# ControlBoard.net
KiCad netlist of a schematic drawn in EAGLE
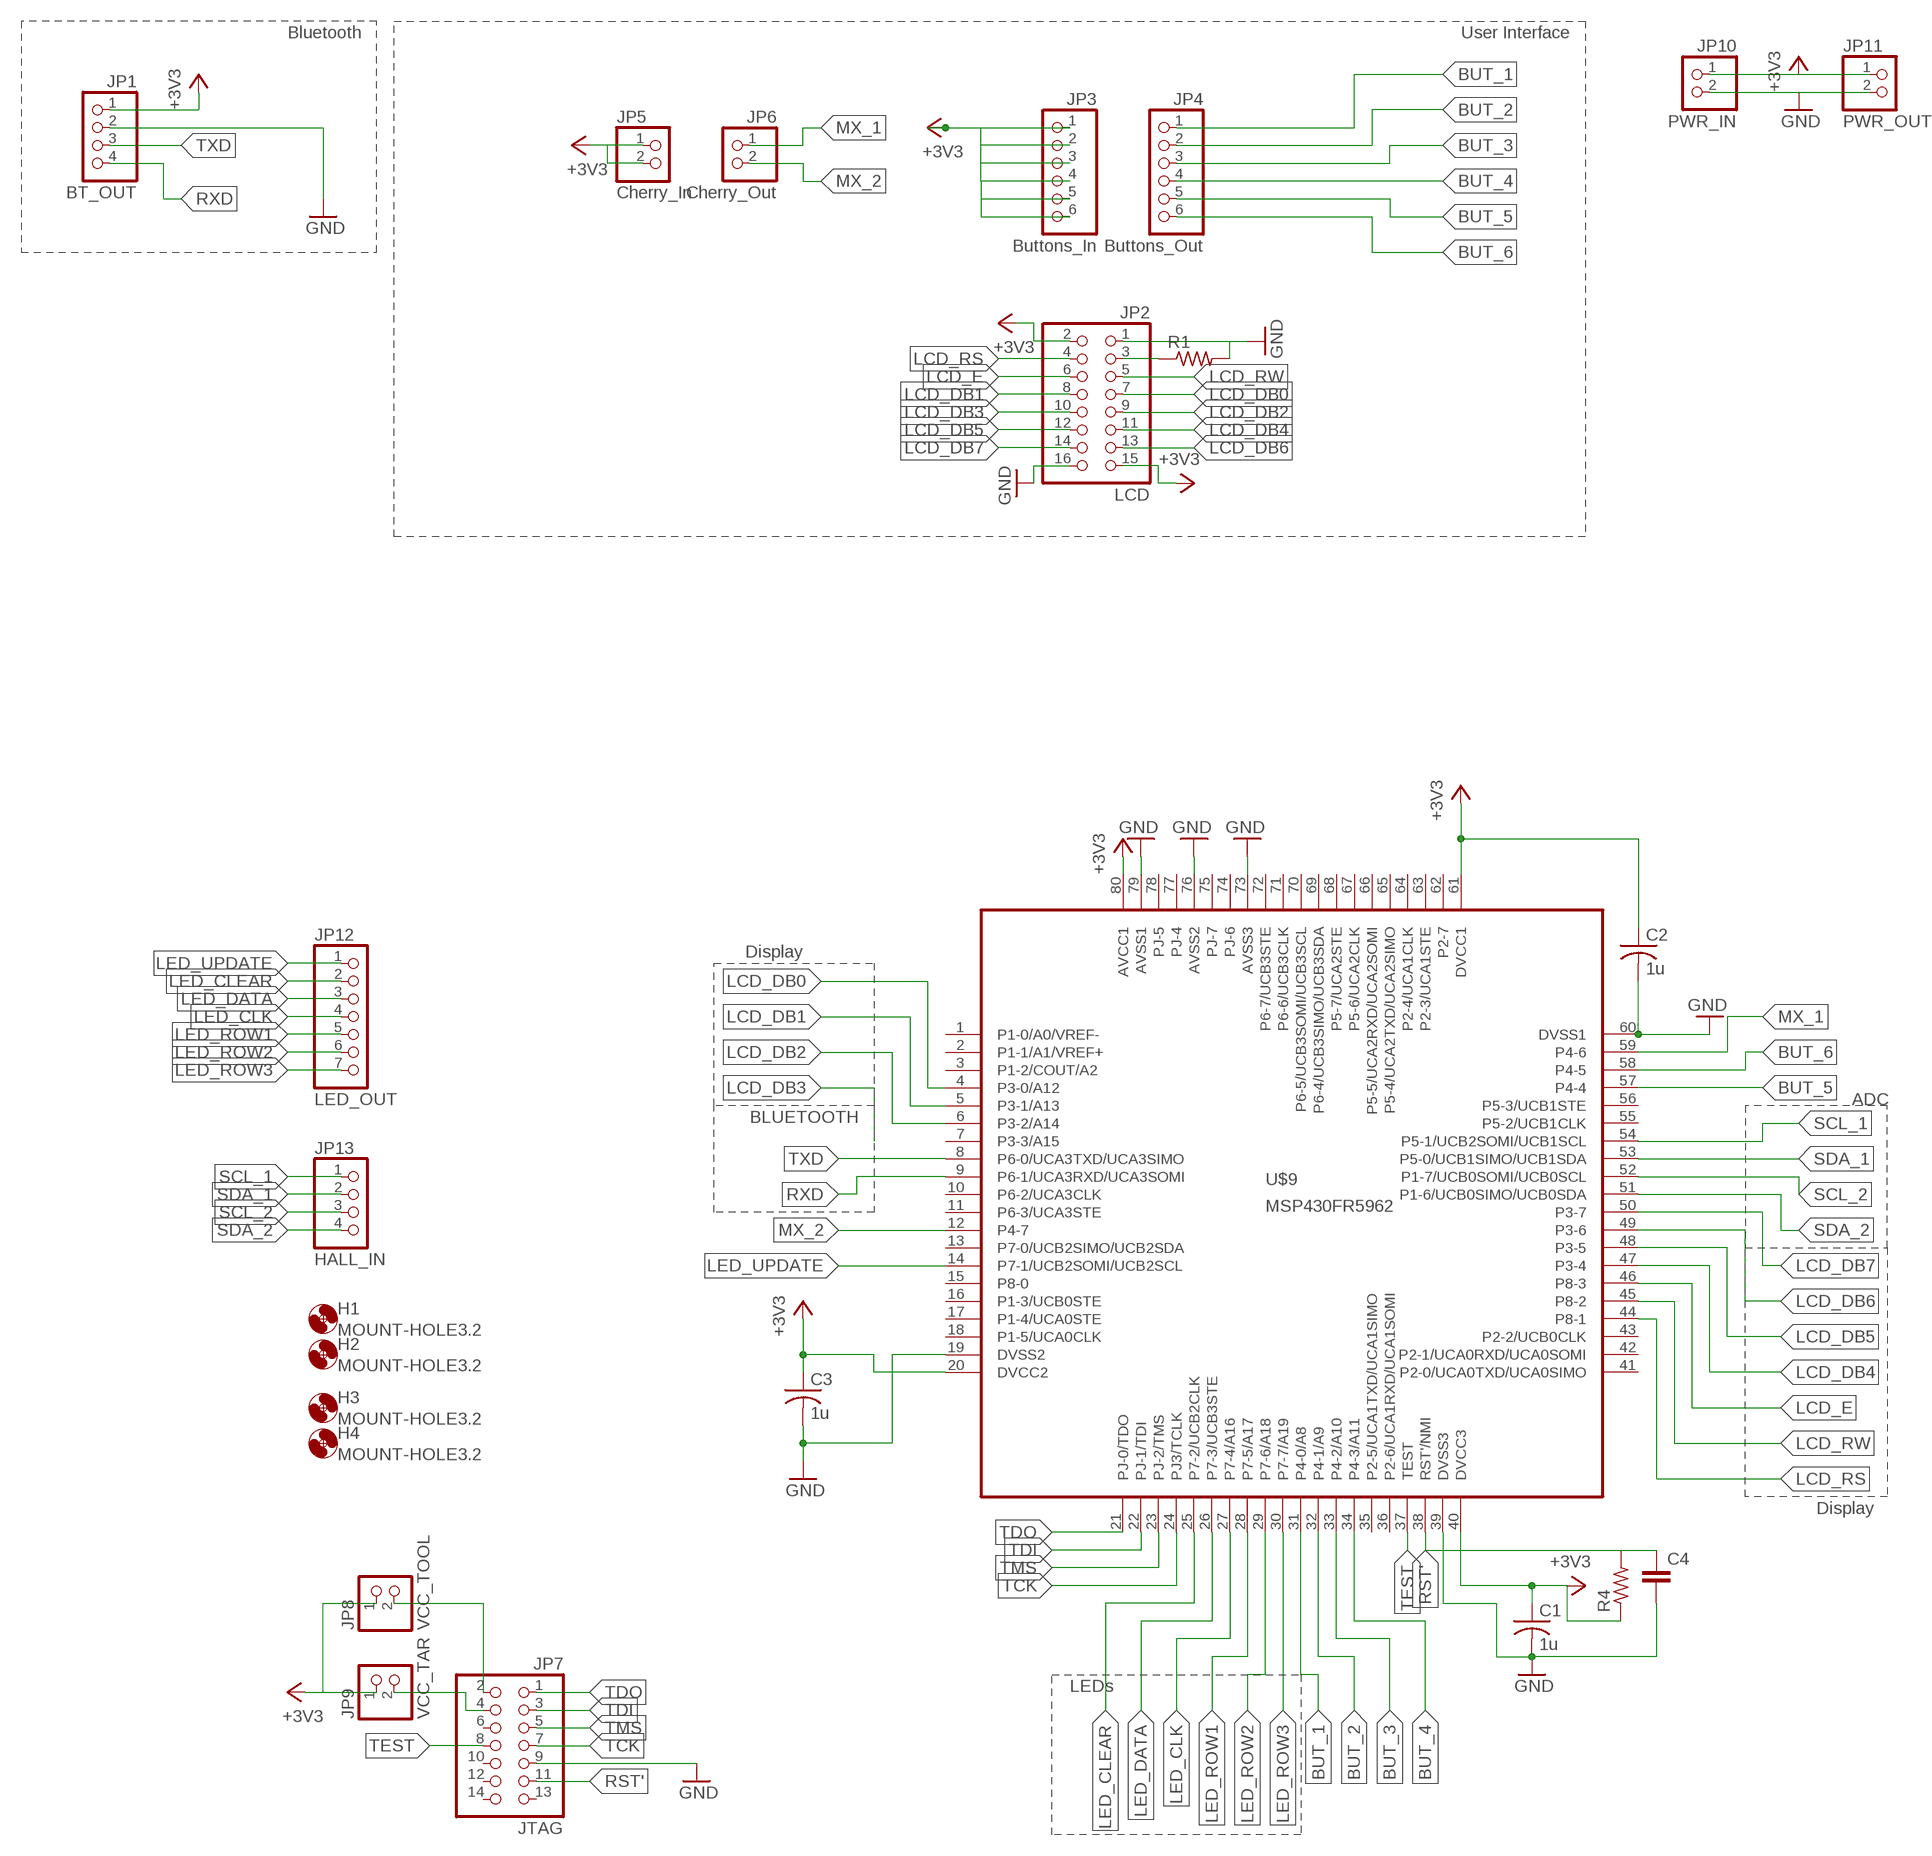
[diagram p0: schematic, sheet 1]

(export (version "E")
  (design (tool "Eeschema 10.0.6"))
  (components
    (comp (ref "C1")
      (value "1u")
      (footprint "eagle-import:C0603")
      (libsource (lib "eagle-import") (part "C-USC0603"))
    )
    (comp (ref "C2")
      (value "1u")
      (footprint "eagle-import:C0603")
      (libsource (lib "eagle-import") (part "C-USC0603"))
    )
    (comp (ref "C3")
      (value "1u")
      (footprint "eagle-import:C0603")
      (libsource (lib "eagle-import") (part "C-USC0603"))
    )
    (comp (ref "C4")
      (value "C-EU025-025X050")
      (footprint "eagle-import:C025-025X050")
      (libsource (lib "eagle-import") (part "C-EU025-025X050"))
    )
    (comp (ref "H1")
      (value "MOUNT-HOLE3.2")
      (footprint "eagle-import:3,2")
      (libsource (lib "eagle-import") (part "MOUNT-HOLE3.2"))
    )
    (comp (ref "H2")
      (value "MOUNT-HOLE3.2")
      (footprint "eagle-import:3,2")
      (libsource (lib "eagle-import") (part "MOUNT-HOLE3.2"))
    )
    (comp (ref "H3")
      (value "MOUNT-HOLE3.2")
      (footprint "eagle-import:3,2")
      (libsource (lib "eagle-import") (part "MOUNT-HOLE3.2"))
    )
    (comp (ref "H4")
      (value "MOUNT-HOLE3.2")
      (footprint "eagle-import:3,2")
      (libsource (lib "eagle-import") (part "MOUNT-HOLE3.2"))
    )
    (comp (ref "JP1")
      (value "BT_OUT")
      (footprint "eagle-import:1X04")
      (libsource (lib "eagle-import") (part "PINHD-1X4"))
    )
    (comp (ref "JP2")
      (value "LCD")
      (footprint "eagle-import:2X08")
      (libsource (lib "eagle-import") (part "PINHD-2X8"))
    )
    (comp (ref "JP3")
      (value "Buttons_In")
      (footprint "eagle-import:1X06")
      (libsource (lib "eagle-import") (part "PINHD-1X6"))
    )
    (comp (ref "JP4")
      (value "Buttons_Out")
      (footprint "eagle-import:1X06")
      (libsource (lib "eagle-import") (part "PINHD-1X6"))
    )
    (comp (ref "JP5")
      (value "Cherry_In")
      (footprint "eagle-import:1X02")
      (libsource (lib "eagle-import") (part "PINHD-1X2"))
    )
    (comp (ref "JP6")
      (value "Cherry_Out")
      (footprint "eagle-import:1X02")
      (libsource (lib "eagle-import") (part "PINHD-1X2"))
    )
    (comp (ref "JP7")
      (value "JTAG")
      (footprint "eagle-import:2X07")
      (libsource (lib "eagle-import") (part "PINHD-2X7"))
    )
    (comp (ref "JP8")
      (value "VCC_TOOL")
      (footprint "eagle-import:1X02")
      (libsource (lib "eagle-import") (part "PINHD-1X2"))
    )
    (comp (ref "JP9")
      (value "VCC_TAR")
      (footprint "eagle-import:1X02")
      (libsource (lib "eagle-import") (part "PINHD-1X2"))
    )
    (comp (ref "JP10")
      (value "PWR_IN")
      (footprint "eagle-import:1X02")
      (libsource (lib "eagle-import") (part "PINHD-1X2"))
    )
    (comp (ref "JP11")
      (value "PWR_OUT")
      (footprint "eagle-import:1X02")
      (libsource (lib "eagle-import") (part "PINHD-1X2"))
    )
    (comp (ref "JP12")
      (value "LED_OUT")
      (footprint "eagle-import:1X07")
      (libsource (lib "eagle-import") (part "PINHD-1X7"))
    )
    (comp (ref "JP13")
      (value "HALL_IN")
      (footprint "eagle-import:1X04")
      (libsource (lib "eagle-import") (part "PINHD-1X4"))
    )
    (comp (ref "R1")
      (value "R-US_VMTA55")
      (footprint "eagle-import:VMTA55")
      (libsource (lib "eagle-import") (part "R-US_VMTA55"))
    )
    (comp (ref "R4")
      (value "R-US_VMTA55")
      (footprint "eagle-import:VMTA55")
      (libsource (lib "eagle-import") (part "R-US_VMTA55"))
    )
    (comp (ref "U$9")
      (value "MSP430FR5962")
      (footprint "eagle-import:LQFP80")
      (libsource (lib "eagle-import") (part "MSP430FR5962"))
    )
  )
  (nets
    (net (code "1") (name "+3V3") (class "Default")
      (node (ref "C1") (pin "1") (pinfunction "1_1") (pintype "passive"))
      (node (ref "C2") (pin "1") (pinfunction "1_1") (pintype "passive"))
      (node (ref "C3") (pin "1") (pinfunction "1_1") (pintype "passive"))
      (node (ref "JP1") (pin "1") (pinfunction "1_1") (pintype "passive"))
      (node (ref "JP10") (pin "1") (pinfunction "1_1") (pintype "passive"))
      (node (ref "JP11") (pin "1") (pinfunction "1_1") (pintype "passive"))
      (node (ref "JP2") (pin "15") (pinfunction "15_15") (pintype "passive"))
      (node (ref "JP2") (pin "2") (pinfunction "2_2") (pintype "passive"))
      (node (ref "JP3") (pin "1") (pinfunction "1_1") (pintype "passive"))
      (node (ref "JP3") (pin "2") (pinfunction "2_2") (pintype "passive"))
      (node (ref "JP3") (pin "3") (pinfunction "3_3") (pintype "passive"))
      (node (ref "JP3") (pin "4") (pinfunction "4_4") (pintype "passive"))
      (node (ref "JP3") (pin "5") (pinfunction "5_5") (pintype "passive"))
      (node (ref "JP3") (pin "6") (pinfunction "6_6") (pintype "passive"))
      (node (ref "JP5") (pin "1") (pinfunction "1_1") (pintype "passive"))
      (node (ref "JP5") (pin "2") (pinfunction "2_2") (pintype "passive"))
      (node (ref "JP8") (pin "1") (pinfunction "1_1") (pintype "passive"))
      (node (ref "JP9") (pin "1") (pinfunction "1_1") (pintype "passive"))
      (node (ref "R4") (pin "1") (pinfunction "1_1") (pintype "passive"))
      (node (ref "U$9") (pin "20") (pinfunction "DVCC2_20") (pintype "bidirectional"))
      (node (ref "U$9") (pin "40") (pinfunction "DVCC3_40") (pintype "bidirectional"))
      (node (ref "U$9") (pin "61") (pinfunction "DVCC1_61") (pintype "bidirectional"))
      (node (ref "U$9") (pin "80") (pinfunction "AVCC1_80") (pintype "power_in"))
    )
    (net (code "2") (name "/P1-0{slash}A0{slash}VREF-") (class "Default")
      (node (ref "U$9") (pin "1") (pinfunction "P1-0/A0/VREF-_1") (pintype "power_in"))
    )
    (net (code "3") (name "/PJ-5") (class "Default")
      (node (ref "U$9") (pin "78") (pinfunction "PJ-5_78") (pintype "power_in"))
    )
    (net (code "4") (name "BUT_1") (class "Default")
      (node (ref "JP4") (pin "1") (pinfunction "1_1") (pintype "passive"))
      (node (ref "U$9") (pin "31") (pinfunction "P4-0/A8_31") (pintype "bidirectional"))
    )
    (net (code "5") (name "BUT_2") (class "Default")
      (node (ref "JP4") (pin "2") (pinfunction "2_2") (pintype "passive"))
      (node (ref "U$9") (pin "32") (pinfunction "P4-1/A9_32") (pintype "output"))
    )
    (net (code "6") (name "BUT_3") (class "Default")
      (node (ref "JP4") (pin "3") (pinfunction "3_3") (pintype "passive"))
      (node (ref "U$9") (pin "33") (pinfunction "P4-2/A10_33") (pintype "output"))
    )
    (net (code "7") (name "BUT_4") (class "Default")
      (node (ref "JP4") (pin "4") (pinfunction "4_4") (pintype "passive"))
      (node (ref "U$9") (pin "34") (pinfunction "P4-3/A11_34") (pintype "output"))
    )
    (net (code "8") (name "BUT_5") (class "Default")
      (node (ref "JP4") (pin "5") (pinfunction "5_5") (pintype "passive"))
      (node (ref "U$9") (pin "57") (pinfunction "P4-4_57") (pintype "bidirectional"))
    )
    (net (code "9") (name "BUT_6") (class "Default")
      (node (ref "JP4") (pin "6") (pinfunction "6_6") (pintype "passive"))
      (node (ref "U$9") (pin "58") (pinfunction "P4-5_58") (pintype "bidirectional"))
    )
    (net (code "10") (name "GND") (class "Default")
      (node (ref "C1") (pin "2") (pinfunction "2_2") (pintype "passive"))
      (node (ref "C2") (pin "2") (pinfunction "2_2") (pintype "passive"))
      (node (ref "C3") (pin "2") (pinfunction "2_2") (pintype "passive"))
      (node (ref "C4") (pin "2") (pinfunction "2_2") (pintype "passive"))
      (node (ref "JP1") (pin "2") (pinfunction "2_2") (pintype "passive"))
      (node (ref "JP10") (pin "2") (pinfunction "2_2") (pintype "passive"))
      (node (ref "JP11") (pin "2") (pinfunction "2_2") (pintype "passive"))
      (node (ref "JP2") (pin "1") (pinfunction "1_1") (pintype "passive"))
      (node (ref "JP2") (pin "16") (pinfunction "16_16") (pintype "passive"))
      (node (ref "JP7") (pin "9") (pinfunction "9_9") (pintype "passive"))
      (node (ref "R1") (pin "2") (pinfunction "2_2") (pintype "passive"))
      (node (ref "U$9") (pin "19") (pinfunction "DVSS2_19") (pintype "bidirectional"))
      (node (ref "U$9") (pin "39") (pinfunction "DVSS3_39") (pintype "bidirectional"))
      (node (ref "U$9") (pin "60") (pinfunction "DVSS1_60") (pintype "bidirectional"))
      (node (ref "U$9") (pin "73") (pinfunction "AVSS3_73") (pintype "input"))
      (node (ref "U$9") (pin "76") (pinfunction "AVSS2_76") (pintype "bidirectional"))
      (node (ref "U$9") (pin "79") (pinfunction "AVSS1_79") (pintype "power_in"))
    )
    (net (code "11") (name "LCD_DB0") (class "Default")
      (node (ref "JP2") (pin "7") (pinfunction "7_7") (pintype "passive"))
      (node (ref "U$9") (pin "4") (pinfunction "P3-0/A12_4") (pintype "bidirectional"))
    )
    (net (code "12") (name "LCD_DB1") (class "Default")
      (node (ref "JP2") (pin "8") (pinfunction "8_8") (pintype "passive"))
      (node (ref "U$9") (pin "5") (pinfunction "P3-1/A13_5") (pintype "bidirectional"))
    )
    (net (code "13") (name "LCD_DB2") (class "Default")
      (node (ref "JP2") (pin "9") (pinfunction "9_9") (pintype "passive"))
      (node (ref "U$9") (pin "6") (pinfunction "P3-2/A14_6") (pintype "bidirectional"))
    )
    (net (code "14") (name "LCD_DB3") (class "Default")
      (node (ref "JP2") (pin "10") (pinfunction "10_10") (pintype "passive"))
    )
    (net (code "15") (name "LCD_DB4") (class "Default")
      (node (ref "JP2") (pin "11") (pinfunction "11_11") (pintype "passive"))
      (node (ref "U$9") (pin "47") (pinfunction "P3-4_47") (pintype "bidirectional"))
    )
    (net (code "16") (name "LCD_DB5") (class "Default")
      (node (ref "JP2") (pin "12") (pinfunction "12_12") (pintype "passive"))
      (node (ref "U$9") (pin "48") (pinfunction "P3-5_48") (pintype "bidirectional"))
    )
    (net (code "17") (name "LCD_DB6") (class "Default")
      (node (ref "JP2") (pin "13") (pinfunction "13_13") (pintype "passive"))
      (node (ref "U$9") (pin "49") (pinfunction "P3-6_49") (pintype "input"))
    )
    (net (code "18") (name "LCD_DB7") (class "Default")
      (node (ref "JP2") (pin "14") (pinfunction "14_14") (pintype "passive"))
      (node (ref "U$9") (pin "50") (pinfunction "P3-7_50") (pintype "bidirectional"))
    )
    (net (code "19") (name "LCD_E") (class "Default")
      (node (ref "JP2") (pin "6") (pinfunction "6_6") (pintype "passive"))
      (node (ref "U$9") (pin "46") (pinfunction "P8-3_46") (pintype "bidirectional"))
    )
    (net (code "20") (name "LCD_RS") (class "Default")
      (node (ref "JP2") (pin "4") (pinfunction "4_4") (pintype "passive"))
      (node (ref "U$9") (pin "44") (pinfunction "P8-1_44") (pintype "bidirectional"))
    )
    (net (code "21") (name "LCD_RW") (class "Default")
      (node (ref "JP2") (pin "5") (pinfunction "5_5") (pintype "passive"))
      (node (ref "U$9") (pin "45") (pinfunction "P8-2_45") (pintype "output"))
    )
    (net (code "22") (name "LED_CLEAR") (class "Default")
      (node (ref "JP12") (pin "2") (pinfunction "2_2") (pintype "passive"))
      (node (ref "U$9") (pin "25") (pinfunction "P7-2/UCB2CLK_25") (pintype "output"))
    )
    (net (code "23") (name "LED_CLK") (class "Default")
      (node (ref "JP12") (pin "4") (pinfunction "4_4") (pintype "passive"))
      (node (ref "U$9") (pin "27") (pinfunction "P7-4/A16_27") (pintype "output"))
    )
    (net (code "24") (name "LED_DATA") (class "Default")
      (node (ref "JP12") (pin "3") (pinfunction "3_3") (pintype "passive"))
      (node (ref "U$9") (pin "26") (pinfunction "P7-3/UCB3STE_26") (pintype "output"))
    )
    (net (code "25") (name "LED_ROW1") (class "Default")
      (node (ref "JP12") (pin "5") (pinfunction "5_5") (pintype "passive"))
      (node (ref "U$9") (pin "28") (pinfunction "P7-5/A17_28") (pintype "output"))
    )
    (net (code "26") (name "LED_ROW2") (class "Default")
      (node (ref "JP12") (pin "6") (pinfunction "6_6") (pintype "passive"))
      (node (ref "U$9") (pin "29") (pinfunction "P7-6/A18_29") (pintype "output"))
    )
    (net (code "27") (name "LED_ROW3") (class "Default")
      (node (ref "JP12") (pin "7") (pinfunction "7_7") (pintype "passive"))
      (node (ref "U$9") (pin "30") (pinfunction "P7-7/A19_30") (pintype "bidirectional"))
    )
    (net (code "28") (name "LED_UPDATE") (class "Default")
      (node (ref "JP12") (pin "1") (pinfunction "1_1") (pintype "passive"))
      (node (ref "U$9") (pin "14") (pinfunction "P7-1/UCB2SOMI/UCB2SCL_14") (pintype "bidirectional"))
    )
    (net (code "29") (name "MX_1") (class "Default")
      (node (ref "JP6") (pin "1") (pinfunction "1_1") (pintype "passive"))
      (node (ref "U$9") (pin "59") (pinfunction "P4-6_59") (pintype "bidirectional"))
    )
    (net (code "30") (name "MX_2") (class "Default")
      (node (ref "JP6") (pin "2") (pinfunction "2_2") (pintype "passive"))
      (node (ref "U$9") (pin "12") (pinfunction "P4-7_12") (pintype "bidirectional"))
    )
    (net (code "31") (name "Net-(JP2-Pad3)") (class "Default")
      (node (ref "JP2") (pin "3") (pinfunction "3_3") (pintype "passive"))
      (node (ref "R1") (pin "1") (pinfunction "1_1") (pintype "passive"))
    )
    (net (code "32") (name "Net-(JP7-Pad2)") (class "Default")
      (node (ref "JP7") (pin "2") (pinfunction "2_2") (pintype "passive"))
      (node (ref "JP8") (pin "2") (pinfunction "2_2") (pintype "passive"))
    )
    (net (code "33") (name "Net-(JP7-Pad4)") (class "Default")
      (node (ref "JP7") (pin "4") (pinfunction "4_4") (pintype "passive"))
      (node (ref "JP9") (pin "2") (pinfunction "2_2") (pintype "passive"))
    )
    (net (code "34") (name "RST'") (class "Default")
      (node (ref "C4") (pin "1") (pinfunction "1_1") (pintype "passive"))
      (node (ref "JP7") (pin "11") (pinfunction "11_11") (pintype "passive"))
      (node (ref "R4") (pin "2") (pinfunction "2_2") (pintype "passive"))
      (node (ref "U$9") (pin "38") (pinfunction "RST'/NMI_38") (pintype "bidirectional"))
    )
    (net (code "35") (name "RXD") (class "Default")
      (node (ref "JP1") (pin "4") (pinfunction "4_4") (pintype "passive"))
      (node (ref "U$9") (pin "9") (pinfunction "P6-1/UCA3RXD/UCA3SOMI_9") (pintype "output"))
    )
    (net (code "36") (name "SCL_1") (class "Default")
      (node (ref "JP13") (pin "1") (pinfunction "1_1") (pintype "passive"))
      (node (ref "U$9") (pin "54") (pinfunction "P5-1/UCB2SOMI/UCB1SCL_54") (pintype "power_in"))
    )
    (net (code "37") (name "SCL_2") (class "Default")
      (node (ref "JP13") (pin "3") (pinfunction "3_3") (pintype "passive"))
      (node (ref "U$9") (pin "52") (pinfunction "P1-7/UCB0SOMI/UCB0SCL_52") (pintype "bidirectional"))
    )
    (net (code "38") (name "SDA_1") (class "Default")
      (node (ref "JP13") (pin "2") (pinfunction "2_2") (pintype "passive"))
      (node (ref "U$9") (pin "53") (pinfunction "P5-0/UCB1SIMO/UCB1SDA_53") (pintype "power_in"))
    )
    (net (code "39") (name "SDA_2") (class "Default")
      (node (ref "JP13") (pin "4") (pinfunction "4_4") (pintype "passive"))
      (node (ref "U$9") (pin "51") (pinfunction "P1-6/UCB0SIMO/UCB0SDA_51") (pintype "bidirectional"))
    )
    (net (code "40") (name "TCK") (class "Default")
      (node (ref "JP7") (pin "7") (pinfunction "7_7") (pintype "passive"))
      (node (ref "U$9") (pin "24") (pinfunction "PJ3/TCLK_24") (pintype "output"))
    )
    (net (code "41") (name "TDI") (class "Default")
      (node (ref "JP7") (pin "3") (pinfunction "3_3") (pintype "passive"))
      (node (ref "U$9") (pin "22") (pinfunction "PJ-1/TDI_22") (pintype "output"))
    )
    (net (code "42") (name "TDO") (class "Default")
      (node (ref "JP7") (pin "1") (pinfunction "1_1") (pintype "passive"))
      (node (ref "U$9") (pin "21") (pinfunction "PJ-0/TDO_21") (pintype "bidirectional"))
    )
    (net (code "43") (name "TEST") (class "Default")
      (node (ref "JP7") (pin "8") (pinfunction "8_8") (pintype "passive"))
      (node (ref "U$9") (pin "37") (pinfunction "TEST_37") (pintype "bidirectional"))
    )
    (net (code "44") (name "TMS") (class "Default")
      (node (ref "JP7") (pin "5") (pinfunction "5_5") (pintype "passive"))
      (node (ref "U$9") (pin "23") (pinfunction "PJ-2/TMS_23") (pintype "output"))
    )
    (net (code "45") (name "TXD") (class "Default")
      (node (ref "JP1") (pin "3") (pinfunction "3_3") (pintype "passive"))
      (node (ref "U$9") (pin "8") (pinfunction "P6-0/UCA3TXD/UCA3SIMO_8") (pintype "input"))
    )
    (net (code "46") (name "unconnected-(JP7-Pad6)") (class "Default")
      (node (ref "JP7") (pin "6") (pinfunction "6_6") (pintype "passive"))
    )
    (net (code "47") (name "unconnected-(JP7-Pad10)") (class "Default")
      (node (ref "JP7") (pin "10") (pinfunction "10_10") (pintype "passive"))
    )
    (net (code "48") (name "unconnected-(JP7-Pad12)") (class "Default")
      (node (ref "JP7") (pin "12") (pinfunction "12_12") (pintype "passive"))
    )
    (net (code "49") (name "unconnected-(JP7-Pad13)") (class "Default")
      (node (ref "JP7") (pin "13") (pinfunction "13_13") (pintype "passive"))
    )
    (net (code "50") (name "unconnected-(JP7-Pad14)") (class "Default")
      (node (ref "JP7") (pin "14") (pinfunction "14_14") (pintype "passive"))
    )
    (net (code "51") (name "unconnected-(U$9-P1-1{slash}A1{slash}VREF+-Pad2)") (class "Default")
      (node (ref "U$9") (pin "2") (pinfunction "P1-1/A1/VREF+_2") (pintype "bidirectional"))
    )
    (net (code "52") (name "unconnected-(U$9-P1-2{slash}COUT{slash}A2-Pad3)") (class "Default")
      (node (ref "U$9") (pin "3") (pinfunction "P1-2/COUT/A2_3") (pintype "bidirectional"))
    )
    (net (code "53") (name "unconnected-(U$9-P1-3{slash}UCB0STE-Pad16)") (class "Default")
      (node (ref "U$9") (pin "16") (pinfunction "P1-3/UCB0STE_16") (pintype "bidirectional"))
    )
    (net (code "54") (name "unconnected-(U$9-P1-4{slash}UCA0STE-Pad17)") (class "Default")
      (node (ref "U$9") (pin "17") (pinfunction "P1-4/UCA0STE_17") (pintype "bidirectional"))
    )
    (net (code "55") (name "unconnected-(U$9-P1-5{slash}UCA0CLK-Pad18)") (class "Default")
      (node (ref "U$9") (pin "18") (pinfunction "P1-5/UCA0CLK_18") (pintype "bidirectional"))
    )
    (net (code "56") (name "unconnected-(U$9-P2-0{slash}UCA0TXD{slash}UCA0SIMO-Pad41)") (class "Default")
      (node (ref "U$9") (pin "41") (pinfunction "P2-0/UCA0TXD/UCA0SIMO_41") (pintype "bidirectional"))
    )
    (net (code "57") (name "unconnected-(U$9-P2-1{slash}UCA0RXD{slash}UCA0SOMI-Pad42)") (class "Default")
      (node (ref "U$9") (pin "42") (pinfunction "P2-1/UCA0RXD/UCA0SOMI_42") (pintype "bidirectional"))
    )
    (net (code "58") (name "unconnected-(U$9-P2-2{slash}UCB0CLK-Pad43)") (class "Default")
      (node (ref "U$9") (pin "43") (pinfunction "P2-2/UCB0CLK_43") (pintype "bidirectional"))
    )
    (net (code "59") (name "unconnected-(U$9-P2-3{slash}UCA1STE-Pad63)") (class "Default")
      (node (ref "U$9") (pin "63") (pinfunction "P2-3/UCA1STE_63") (pintype "bidirectional"))
    )
    (net (code "60") (name "unconnected-(U$9-P2-4{slash}UCA1CLK-Pad64)") (class "Default")
      (node (ref "U$9") (pin "64") (pinfunction "P2-4/UCA1CLK_64") (pintype "bidirectional"))
    )
    (net (code "61") (name "unconnected-(U$9-P2-5{slash}UCA1TXD{slash}UCA1SIMO-Pad35)") (class "Default")
      (node (ref "U$9") (pin "35") (pinfunction "P2-5/UCA1TXD/UCA1SIMO_35") (pintype "output"))
    )
    (net (code "62") (name "unconnected-(U$9-P2-6{slash}UCA1RXD{slash}UCA1SOMI-Pad36)") (class "Default")
      (node (ref "U$9") (pin "36") (pinfunction "P2-6/UCA1RXD/UCA1SOMI_36") (pintype "bidirectional"))
    )
    (net (code "63") (name "unconnected-(U$9-P2-7-Pad62)") (class "Default")
      (node (ref "U$9") (pin "62") (pinfunction "P2-7_62") (pintype "bidirectional"))
    )
    (net (code "64") (name "unconnected-(U$9-P3-3{slash}A15-Pad7)") (class "Default")
      (node (ref "U$9") (pin "7") (pinfunction "P3-3/A15_7") (pintype "output"))
    )
    (net (code "65") (name "unconnected-(U$9-P5-2{slash}UCB1CLK-Pad55)") (class "Default")
      (node (ref "U$9") (pin "55") (pinfunction "P5-2/UCB1CLK_55") (pintype "bidirectional"))
    )
    (net (code "66") (name "unconnected-(U$9-P5-3{slash}UCB1STE-Pad56)") (class "Default")
      (node (ref "U$9") (pin "56") (pinfunction "P5-3/UCB1STE_56") (pintype "bidirectional"))
    )
    (net (code "67") (name "unconnected-(U$9-P5-4{slash}UCA2TXD{slash}UCA2SIMO-Pad65)") (class "Default")
      (node (ref "U$9") (pin "65") (pinfunction "P5-4/UCA2TXD/UCA2SIMO_65") (pintype "bidirectional"))
    )
    (net (code "68") (name "unconnected-(U$9-P5-5{slash}UCA2RXD{slash}UCA2SOMI-Pad66)") (class "Default")
      (node (ref "U$9") (pin "66") (pinfunction "P5-5/UCA2RXD/UCA2SOMI_66") (pintype "bidirectional"))
    )
    (net (code "69") (name "unconnected-(U$9-P5-6{slash}UCA2CLK-Pad67)") (class "Default")
      (node (ref "U$9") (pin "67") (pinfunction "P5-6/UCA2CLK_67") (pintype "bidirectional"))
    )
    (net (code "70") (name "unconnected-(U$9-P5-7{slash}UCA2STE-Pad68)") (class "Default")
      (node (ref "U$9") (pin "68") (pinfunction "P5-7/UCA2STE_68") (pintype "output"))
    )
    (net (code "71") (name "unconnected-(U$9-P6-2{slash}UCA3CLK-Pad10)") (class "Default")
      (node (ref "U$9") (pin "10") (pinfunction "P6-2/UCA3CLK_10") (pintype "bidirectional"))
    )
    (net (code "72") (name "unconnected-(U$9-P6-3{slash}UCA3STE-Pad11)") (class "Default")
      (node (ref "U$9") (pin "11") (pinfunction "P6-3/UCA3STE_11") (pintype "input"))
    )
    (net (code "73") (name "unconnected-(U$9-P6-4{slash}UCB3SIMO{slash}UCB3SDA-Pad69)") (class "Default")
      (node (ref "U$9") (pin "69") (pinfunction "P6-4/UCB3SIMO/UCB3SDA_69") (pintype "input"))
    )
    (net (code "74") (name "unconnected-(U$9-P6-5{slash}UCB3SOMI{slash}UCB3SCL-Pad70)") (class "Default")
      (node (ref "U$9") (pin "70") (pinfunction "P6-5/UCB3SOMI/UCB3SCL_70") (pintype "bidirectional"))
    )
    (net (code "75") (name "unconnected-(U$9-P6-6{slash}UCB3CLK-Pad71)") (class "Default")
      (node (ref "U$9") (pin "71") (pinfunction "P6-6/UCB3CLK_71") (pintype "input"))
    )
    (net (code "76") (name "unconnected-(U$9-P6-7{slash}UCB3STE-Pad72)") (class "Default")
      (node (ref "U$9") (pin "72") (pinfunction "P6-7/UCB3STE_72") (pintype "input"))
    )
    (net (code "77") (name "unconnected-(U$9-P7-0{slash}UCB2SIMO{slash}UCB2SDA-Pad13)") (class "Default")
      (node (ref "U$9") (pin "13") (pinfunction "P7-0/UCB2SIMO/UCB2SDA_13") (pintype "bidirectional"))
    )
    (net (code "78") (name "unconnected-(U$9-P8-0-Pad15)") (class "Default")
      (node (ref "U$9") (pin "15") (pinfunction "P8-0_15") (pintype "bidirectional"))
    )
    (net (code "79") (name "unconnected-(U$9-PJ-4-Pad77)") (class "Default")
      (node (ref "U$9") (pin "77") (pinfunction "PJ-4_77") (pintype "bidirectional"))
    )
    (net (code "80") (name "unconnected-(U$9-PJ-6-Pad74)") (class "Default")
      (node (ref "U$9") (pin "74") (pinfunction "PJ-6_74") (pintype "input"))
    )
    (net (code "81") (name "unconnected-(U$9-PJ-7-Pad75)") (class "Default")
      (node (ref "U$9") (pin "75") (pinfunction "PJ-7_75") (pintype "bidirectional"))
    )
  )
)
